# floppy_m0dule.net
KiCad netlist of a schematic drawn in Altium Designer
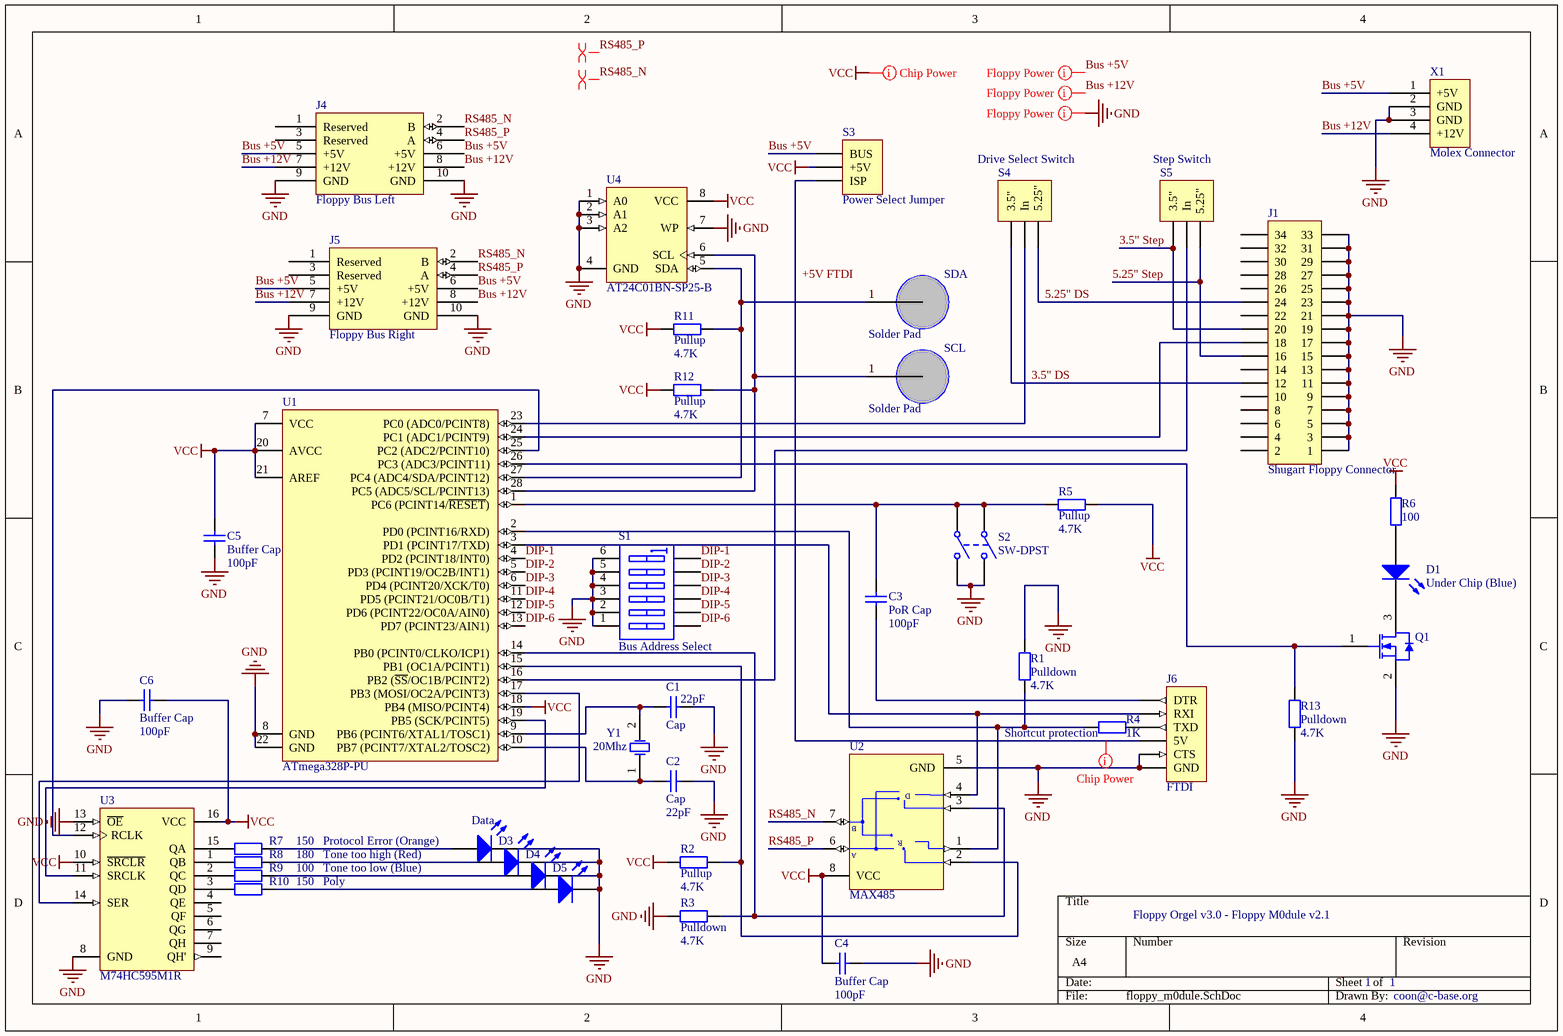
[diagram p0: floppy_m0dule.SchDoc]

(export (version "E")
  (design (tool "Eeschema 10.0.6"))
  (components
    (comp (ref "C1")
      (value "Cap")
      (footprint "RAD-0.1")
      (description "Capacitor")
      (fields (field (name "ALTIUM_VALUE") "22pF") (field (name "PUBLISHER") "Altium Limited"))
      (libsource (lib "Miscellaneous Devices") (part "Cap"))
    )
    (comp (ref "C2")
      (value "Cap")
      (footprint "RAD-0.1")
      (description "Capacitor")
      (fields (field (name "ALTIUM_VALUE") "22pF") (field (name "PUBLISHER") "Altium Limited"))
      (libsource (lib "Miscellaneous Devices") (part "Cap"))
    )
    (comp (ref "C3")
      (value "PoR Cap")
      (footprint "RAD-0.1")
      (description "Capacitor")
      (fields (field (name "ALTIUM_VALUE") "100pF") (field (name "PUBLISHER") "Altium Limited"))
      (libsource (lib "Miscellaneous Devices") (part "Cap"))
    )
    (comp (ref "C4")
      (value "Buffer Cap")
      (footprint "C1206")
      (description "Capacitor (Semiconductor SIM Model)")
      (fields (field (name "ALTIUM_VALUE") "100pF") (field (name "PUBLISHER") "Altium Limited"))
      (libsource (lib "Miscellaneous Devices") (part "Cap Semi"))
    )
    (comp (ref "C5")
      (value "Buffer Cap")
      (footprint "C1206")
      (description "Capacitor (Semiconductor SIM Model)")
      (fields (field (name "ALTIUM_VALUE") "100pF") (field (name "PUBLISHER") "Altium Limited"))
      (libsource (lib "Miscellaneous Devices") (part "Cap Semi"))
    )
    (comp (ref "C6")
      (value "Buffer Cap")
      (footprint "C1206")
      (description "Capacitor (Semiconductor SIM Model)")
      (fields (field (name "ALTIUM_VALUE") "100pF") (field (name "PUBLISHER") "Altium Limited"))
      (libsource (lib "Miscellaneous Devices") (part "Cap Semi"))
    )
    (comp (ref "D1")
      (value "Under Chip (Blue)")
      (footprint "0805 LED")
      (description "Typical BLUE SiC LED")
      (fields (field (name "PUBLISHER") "Altium Limited"))
      (libsource (lib "Miscellaneous Devices") (part "LED3"))
    )
    (comp (ref "D3")
      (value "Tone too high (Red)")
      (footprint "0805 LED")
      (description "Typical BLUE SiC LED")
      (fields (field (name "PUBLISHER") "Altium Limited"))
      (libsource (lib "Miscellaneous Devices") (part "LED3"))
    )
    (comp (ref "D4")
      (value "Tone too low (Blue)")
      (footprint "0805 LED")
      (description "Typical BLUE SiC LED")
      (fields (field (name "PUBLISHER") "Altium Limited"))
      (libsource (lib "Miscellaneous Devices") (part "LED3"))
    )
    (comp (ref "D5")
      (value "Poly")
      (footprint "0805 LED")
      (description "Typical BLUE SiC LED")
      (fields (field (name "PUBLISHER") "Altium Limited"))
      (libsource (lib "Miscellaneous Devices") (part "LED3"))
    )
    (comp (ref "Data")
      (value "Protocol Error (Orange)")
      (footprint "0805 LED")
      (description "Typical BLUE SiC LED")
      (fields (field (name "PUBLISHER") "Altium Limited"))
      (libsource (lib "Miscellaneous Devices") (part "LED3"))
    )
    (comp (ref "J1")
      (value "Shugart Floppy Connector")
      (footprint "HDR2X17")
      (description "Header, 17-Pin, Dual row")
      (fields (field (name "PUBLISHER") "Altium Limited"))
      (libsource (lib "Miscellaneous Connectors") (part "Header 17X2"))
    )
    (comp (ref "J4")
      (value "Floppy Bus Left")
      (footprint "Shrouded Pinheader 2x5")
      (description "10 Pin Floppy bus connector for rainbow cable")
      (fields (field (name "PUBLISHER") "Altium Limited"))
      (libsource (lib "floppyorgel") (part "Floppy Bus Connector"))
    )
    (comp (ref "J5")
      (value "Floppy Bus Right")
      (footprint "Shrouded Pinheader 2x5")
      (description "10 Pin Floppy bus connector for rainbow cable")
      (fields (field (name "PUBLISHER") "Altium Limited"))
      (libsource (lib "floppyorgel") (part "Floppy Bus Connector"))
    )
    (comp (ref "J6")
      (value "FTDI")
      (footprint "HDR1X6")
      (description "Header, 6-Pin")
      (fields (field (name "PUBLISHER") "Altium Limited"))
      (libsource (lib "Miscellaneous Connectors") (part "Header 6"))
    )
    (comp (ref "Q1")
      (value "IRLML6344TRPbF")
      (footprint "AO-SOT23-3_V")
      (description "N-channel Enhancement Mode Field-Effect Transistor; 5.8A/30V")
      (fields (field (name "MANUFACTURER") "Alpha and Omega") (field (name "PARTNUMBER") "AO3400"))
      (libsource (lib "Altium Content Vault") (part "AO-NEMOS-G1S2D3-3"))
    )
    (comp (ref "R1")
      (value "Pulldown")
      (footprint "AXIAL-0.4")
      (description "Resistor")
      (fields (field (name "ALTIUM_VALUE") "4.7K") (field (name "PUBLISHER") "Altium Limited"))
      (libsource (lib "") (part "Res2_1"))
    )
    (comp (ref "R2")
      (value "Pullup")
      (footprint "AXIAL-0.4")
      (description "Resistor")
      (fields (field (name "ALTIUM_VALUE") "4.7K") (field (name "PUBLISHER") "Altium Limited"))
      (libsource (lib "Miscellaneous Devices") (part "Res2"))
    )
    (comp (ref "R3")
      (value "Pulldown")
      (footprint "AXIAL-0.4")
      (description "Resistor")
      (fields (field (name "ALTIUM_VALUE") "4.7K") (field (name "PUBLISHER") "Altium Limited"))
      (libsource (lib "Miscellaneous Devices") (part "Res2"))
    )
    (comp (ref "R4")
      (value "Shortcut protection")
      (footprint "AXIAL-0.4")
      (description "Resistor")
      (fields (field (name "ALTIUM_VALUE") "1K") (field (name "PUBLISHER") "Altium Limited"))
      (libsource (lib "Miscellaneous Devices") (part "Res2"))
    )
    (comp (ref "R5")
      (value "Pullup")
      (footprint "AXIAL-0.4")
      (description "Resistor")
      (fields (field (name "ALTIUM_VALUE") "4.7K") (field (name "PUBLISHER") "Altium Limited"))
      (libsource (lib "Miscellaneous Devices") (part "Res2"))
    )
    (comp (ref "R6")
      (value "100")
      (footprint "R0805")
      (description "Resistor for Blue LED 17.5mA @ 5V")
      (fields (field (name "Comment") "LED res") (field (name "PUBLISHER") "Altium Limited"))
      (libsource (lib "") (part "Res2_1"))
    )
    (comp (ref "R7")
      (value "150")
      (footprint "R0805")
      (description "Resistor for Green LED 19.33mA @ 5V")
      (fields (field (name "Comment") "LED res") (field (name "PUBLISHER") "Altium Limited"))
      (libsource (lib "Miscellaneous Devices") (part "Res2"))
    )
    (comp (ref "R8")
      (value "180")
      (footprint "R0805")
      (description "Resistor for Blue LED 17.5mA @ 5V")
      (fields (field (name "Comment") "LED res") (field (name "PUBLISHER") "Altium Limited"))
      (libsource (lib "") (part "Res2_2"))
    )
    (comp (ref "R9")
      (value "100")
      (footprint "R0805")
      (description "Resistor for Blue LED 17.5mA @ 5V")
      (fields (field (name "Comment") "LED res") (field (name "PUBLISHER") "Altium Limited"))
      (libsource (lib "") (part "Res2_2"))
    )
    (comp (ref "R10")
      (value "150")
      (footprint "R0805")
      (description "Resistor for Blue LED 17.5mA @ 5V")
      (fields (field (name "Comment") "LED res") (field (name "PUBLISHER") "Altium Limited"))
      (libsource (lib "") (part "Res2_2"))
    )
    (comp (ref "R11")
      (value "Pullup")
      (footprint "R0805")
      (description "Resistor")
      (fields (field (name "ALTIUM_VALUE") "4.7K") (field (name "PUBLISHER") "Altium Limited"))
      (libsource (lib "Miscellaneous Devices") (part "Res2"))
    )
    (comp (ref "R12")
      (value "Pullup")
      (footprint "R0805")
      (description "Resistor")
      (fields (field (name "ALTIUM_VALUE") "4.7K") (field (name "PUBLISHER") "Altium Limited"))
      (libsource (lib "Miscellaneous Devices") (part "Res2"))
    )
    (comp (ref "R13")
      (value "Pulldown")
      (footprint "R0805")
      (description "Resistor")
      (fields (field (name "ALTIUM_VALUE") "4.7K") (field (name "PUBLISHER") "Altium Limited"))
      (libsource (lib "") (part "Res2_1"))
    )
    (comp (ref "S1")
      (value "Bus Address Select")
      (footprint "418117170906")
      (description "Midi Channel Select")
      (fields (field (name "PUBLISHER") "Altium Limited"))
      (libsource (lib "Miscellaneous Devices") (part "SW DIP-6"))
    )
    (comp (ref "S2")
      (value "SW-DPST")
      (footprint "SWITCH")
      (description "Double-Pole, Single-Throw Switch")
      (fields (field (name "PUBLISHER") "Altium Limited"))
      (libsource (lib "Miscellaneous Devices") (part "SW-DPST"))
    )
    (comp (ref "S3")
      (value "Power Select Jumper")
      (footprint "HDR1X3")
      (description "Header, 3-Pin, Right Angle")
      (fields (field (name "PUBLISHER") "Altium Limited"))
      (libsource (lib "Miscellaneous Connectors") (part "Header 3H"))
    )
    (comp (ref "S4")
      (value "Drive Select Switch")
      (footprint "0805 SMD Switch Pads")
      (description "Header, 3-Pin")
      (fields (field (name "PUBLISHER") "Altium Limited"))
      (libsource (lib "Miscellaneous Connectors") (part "Header 3"))
    )
    (comp (ref "S5")
      (value "Step Switch")
      (footprint "0805 SMD Switch Pads")
      (description "Header, 3-Pin")
      (fields (field (name "PUBLISHER") "Altium Limited"))
      (libsource (lib "Miscellaneous Connectors") (part "Header 3"))
    )
    (comp (ref "SCL")
      (value "Solder Pad")
      (footprint "SOLDER_PAD")
      (libsource (lib "floppy_m0dule") (part "Solder Pad"))
    )
    (comp (ref "SDA")
      (value "Solder Pad")
      (footprint "SOLDER_PAD")
      (libsource (lib "floppy_m0dule") (part "Solder Pad"))
    )
    (comp (ref "U1")
      (value "ATmega328P-PU")
      (footprint "28P3")
      (fields (field (name "PUBLISHER") "Altium Limited"))
      (libsource (lib "Atmel Microcontroller 8-Bit megaAVR") (part "ATmega328P-PU"))
    )
    (comp (ref "U2")
      (value "MAX485")
      (footprint "PA8")
      (description "Low-Power, Slew-Rate-Limited RS-485/RS-422 Transceiver")
      (fields (field (name "PUBLISHER") "Altium Limited"))
      (libsource (lib "Maxim Communication Transceiver") (part "MAX485EPA"))
    )
    (comp (ref "U3")
      (value "M74HC595M1R")
      (footprint "SO16_N")
      (description "8 Bit Shift Register with Output Latches (3 STATE)")
      (fields (field (name "PUBLISHER") "Altium Limited"))
      (libsource (lib "ST Logic Register") (part "M74HC595M1R"))
    )
    (comp (ref "U4")
      (value "AT24C01BN-SP25-B")
      (footprint "8S1_N")
      (description "1Kbit (128 x 8), 2-wire Bus Automotive Serial EEPROM with Write Protect, 2.5V, 8-Pin SOIC, Bulk")
      (fields (field (name "PUBLISHER") "Altium Limited"))
      (libsource (lib "Atmel Memory Serial EEPROM") (part "AT24C01BN-SP25-B"))
    )
    (comp (ref "X1")
      (value "Molex Connector")
      (footprint "HDR1X4")
      (description "Molex Power Supply Connector")
      (fields (field (name "PUBLISHER") "Altium Limited"))
      (libsource (lib "floppyorgel") (part "Molex Connector"))
    )
    (comp (ref "Y1")
      (value "20Mhz")
      (footprint "crystal")
      (description "Crystal Oscillator")
      (fields (field (name "PUBLISHER") "Altium Limited"))
      (libsource (lib "Miscellaneous Devices") (part "XTAL"))
    )
  )
  (nets
    (net (code "2") (name "/3.5\" DS") (class "Default")
      (node (ref "J1") (pin "12") (pinfunction "12_12") (pintype "passive"))
      (node (ref "S4") (pin "1") (pinfunction "3.5\"_1") (pintype "passive"))
    )
    (net (code "3") (name "/3.5\" Step") (class "Default")
      (node (ref "J1") (pin "20") (pinfunction "20_20") (pintype "passive"))
      (node (ref "S5") (pin "1") (pinfunction "3.5\"_1") (pintype "passive"))
    )
    (net (code "4") (name "/5.25\" DS") (class "Default")
      (node (ref "J1") (pin "24") (pinfunction "24_24") (pintype "passive"))
      (node (ref "S4") (pin "3") (pinfunction "5.25\"_3") (pintype "passive"))
    )
    (net (code "5") (name "/5.25\" Step") (class "Default")
      (node (ref "J1") (pin "16") (pinfunction "16_16") (pintype "passive"))
      (node (ref "S5") (pin "3") (pinfunction "5.25\"_3") (pintype "passive"))
    )
    (net (code "6") (name "/Bus +5V") (class "Default")
      (node (ref "J4") (pin "5") (pinfunction "+5V_5") (pintype "passive"))
      (node (ref "J4") (pin "6") (pinfunction "+5V_6") (pintype "power_in"))
      (node (ref "J5") (pin "5") (pinfunction "+5V_5") (pintype "passive"))
      (node (ref "J5") (pin "6") (pinfunction "+5V_6") (pintype "power_in"))
      (node (ref "S3") (pin "1") (pinfunction "BUS_1") (pintype "power_in"))
      (node (ref "X1") (pin "1") (pinfunction "+5V_1") (pintype "power_in"))
    )
    (net (code "7") (name "/Bus +12V") (class "Default")
      (node (ref "J4") (pin "7") (pinfunction "+12V_7") (pintype "passive"))
      (node (ref "J4") (pin "8") (pinfunction "+12V_8") (pintype "power_in"))
      (node (ref "J5") (pin "7") (pinfunction "+12V_7") (pintype "passive"))
      (node (ref "J5") (pin "8") (pinfunction "+12V_8") (pintype "power_in"))
      (node (ref "X1") (pin "4") (pinfunction "+12V_4") (pintype "power_in"))
    )
    (net (code "8") (name "/DIP-1") (class "Default")
      (node (ref "S1") (pin "12") (pinfunction "B1_12") (pintype "passive"))
      (node (ref "U1") (pin "4") (pinfunction "PD2_(PCINT18/INT0)_4") (pintype "bidirectional"))
    )
    (net (code "9") (name "/DIP-2") (class "Default")
      (node (ref "S1") (pin "11") (pinfunction "B2_11") (pintype "passive"))
      (node (ref "U1") (pin "5") (pinfunction "PD3_(PCINT19/OC2B/INT1)_5") (pintype "bidirectional"))
    )
    (net (code "10") (name "/DIP-3") (class "Default")
      (node (ref "S1") (pin "10") (pinfunction "B3_10") (pintype "passive"))
      (node (ref "U1") (pin "6") (pinfunction "PD4_(PCINT20/XCK/T0)_6") (pintype "bidirectional"))
    )
    (net (code "11") (name "/DIP-4") (class "Default")
      (node (ref "S1") (pin "9") (pinfunction "B4_9") (pintype "passive"))
      (node (ref "U1") (pin "11") (pinfunction "PD5_(PCINT21/OC0B/T1)_11") (pintype "bidirectional"))
    )
    (net (code "12") (name "/DIP-5") (class "Default")
      (node (ref "S1") (pin "8") (pinfunction "B5_8") (pintype "passive"))
      (node (ref "U1") (pin "12") (pinfunction "PD6_(PCINT22/OC0A/AIN0)_12") (pintype "bidirectional"))
    )
    (net (code "13") (name "/DIP-6") (class "Default")
      (node (ref "S1") (pin "7") (pinfunction "B6_7") (pintype "passive"))
      (node (ref "U1") (pin "13") (pinfunction "PD7_(PCINT23/AIN1)_13") (pintype "bidirectional"))
    )
    (net (code "14") (name "/RS485_N") (class "Default")
      (node (ref "J4") (pin "2") (pinfunction "B_2") (pintype "bidirectional"))
      (node (ref "J5") (pin "2") (pinfunction "B_2") (pintype "bidirectional"))
      (node (ref "U2") (pin "7") (pinfunction "B_7") (pintype "bidirectional"))
    )
    (net (code "15") (name "/RS485_P") (class "Default")
      (node (ref "J4") (pin "4") (pinfunction "A_4") (pintype "bidirectional"))
      (node (ref "J5") (pin "4") (pinfunction "A_4") (pintype "bidirectional"))
      (node (ref "U2") (pin "6") (pinfunction "A_6") (pintype "bidirectional"))
    )
    (net (code "16") (name "GND") (class "Default")
      (node (ref "C1") (pin "2") (pinfunction "2_2") (pintype "passive"))
      (node (ref "C2") (pin "2") (pinfunction "2_2") (pintype "passive"))
      (node (ref "C4") (pin "1") (pinfunction "1_1") (pintype "passive"))
      (node (ref "C5") (pin "1") (pinfunction "1_1") (pintype "passive"))
      (node (ref "C6") (pin "1") (pinfunction "1_1") (pintype "passive"))
      (node (ref "D3") (pin "2") (pinfunction "K_2") (pintype "passive"))
      (node (ref "D4") (pin "2") (pinfunction "K_2") (pintype "passive"))
      (node (ref "D5") (pin "2") (pinfunction "K_2") (pintype "passive"))
      (node (ref "Data") (pin "2") (pinfunction "K_2") (pintype "passive"))
      (node (ref "J1") (pin "1") (pinfunction "1_1") (pintype "passive"))
      (node (ref "J1") (pin "11") (pinfunction "11_11") (pintype "passive"))
      (node (ref "J1") (pin "13") (pinfunction "13_13") (pintype "passive"))
      (node (ref "J1") (pin "15") (pinfunction "15_15") (pintype "passive"))
      (node (ref "J1") (pin "17") (pinfunction "17_17") (pintype "passive"))
      (node (ref "J1") (pin "19") (pinfunction "19_19") (pintype "passive"))
      (node (ref "J1") (pin "21") (pinfunction "21_21") (pintype "passive"))
      (node (ref "J1") (pin "23") (pinfunction "23_23") (pintype "passive"))
      (node (ref "J1") (pin "25") (pinfunction "25_25") (pintype "passive"))
      (node (ref "J1") (pin "27") (pinfunction "27_27") (pintype "passive"))
      (node (ref "J1") (pin "29") (pinfunction "29_29") (pintype "passive"))
      (node (ref "J1") (pin "3") (pinfunction "3_3") (pintype "passive"))
      (node (ref "J1") (pin "31") (pinfunction "31_31") (pintype "passive"))
      (node (ref "J1") (pin "33") (pinfunction "33_33") (pintype "passive"))
      (node (ref "J1") (pin "5") (pinfunction "5_5") (pintype "passive"))
      (node (ref "J1") (pin "7") (pinfunction "7_7") (pintype "passive"))
      (node (ref "J1") (pin "9") (pinfunction "9_9") (pintype "passive"))
      (node (ref "J4") (pin "10") (pinfunction "GND_10") (pintype "passive"))
      (node (ref "J4") (pin "9") (pinfunction "GND_9") (pintype "power_in"))
      (node (ref "J5") (pin "10") (pinfunction "GND_10") (pintype "passive"))
      (node (ref "J5") (pin "9") (pinfunction "GND_9") (pintype "power_in"))
      (node (ref "J6") (pin "5") (pinfunction "CTS_5") (pintype "input"))
      (node (ref "J6") (pin "6") (pinfunction "GND_6") (pintype "power_in"))
      (node (ref "Q1") (pin "2") (pinfunction "S_2") (pintype "passive"))
      (node (ref "R1") (pin "2") (pinfunction "2_2") (pintype "passive"))
      (node (ref "R13") (pin "1") (pinfunction "1_1") (pintype "passive"))
      (node (ref "R3") (pin "1") (pinfunction "1_1") (pintype "passive"))
      (node (ref "S1") (pin "1") (pinfunction "A1_1") (pintype "passive"))
      (node (ref "S1") (pin "2") (pinfunction "A2_2") (pintype "passive"))
      (node (ref "S1") (pin "3") (pinfunction "A3_3") (pintype "passive"))
      (node (ref "S1") (pin "4") (pinfunction "A4_4") (pintype "passive"))
      (node (ref "S1") (pin "5") (pinfunction "A5_5") (pintype "passive"))
      (node (ref "S1") (pin "6") (pinfunction "A6_6") (pintype "passive"))
      (node (ref "S2") (pin "2") (pinfunction "NO1_2") (pintype "passive"))
      (node (ref "S2") (pin "4") (pinfunction "NO2_4") (pintype "passive"))
      (node (ref "U1") (pin "22") (pinfunction "GND_22") (pintype "power_in"))
      (node (ref "U1") (pin "8") (pinfunction "GND_8") (pintype "power_in"))
      (node (ref "U2") (pin "5") (pinfunction "GND_5") (pintype "power_in"))
      (node (ref "U3") (pin "13") (pinfunction "~{OE}_13") (pintype "input"))
      (node (ref "U3") (pin "8") (pinfunction "GND_8") (pintype "power_in"))
      (node (ref "U4") (pin "1") (pinfunction "A0_1") (pintype "input"))
      (node (ref "U4") (pin "2") (pinfunction "A1_2") (pintype "input"))
      (node (ref "U4") (pin "3") (pinfunction "A2_3") (pintype "input"))
      (node (ref "U4") (pin "4") (pinfunction "GND_4") (pintype "power_in"))
      (node (ref "U4") (pin "7") (pinfunction "WP_7") (pintype "input"))
      (node (ref "X1") (pin "2") (pinfunction "GND_2") (pintype "power_in"))
      (node (ref "X1") (pin "3") (pinfunction "GND_3") (pintype "power_in"))
    )
    (net (code "17") (name "Net-(D1-A)") (class "Default")
      (node (ref "D1") (pin "1") (pinfunction "A_1") (pintype "passive"))
      (node (ref "R6") (pin "1") (pinfunction "1_1") (pintype "passive"))
    )
    (net (code "18") (name "Net-(D1-K)") (class "Default")
      (node (ref "D1") (pin "2") (pinfunction "K_2") (pintype "passive"))
      (node (ref "Q1") (pin "3") (pinfunction "D_3") (pintype "passive"))
    )
    (net (code "19") (name "Net-(D3-A)") (class "Default")
      (node (ref "D3") (pin "1") (pinfunction "A_1") (pintype "passive"))
      (node (ref "R8") (pin "1") (pinfunction "1_1") (pintype "passive"))
    )
    (net (code "20") (name "Net-(D4-A)") (class "Default")
      (node (ref "D4") (pin "1") (pinfunction "A_1") (pintype "passive"))
      (node (ref "R9") (pin "1") (pinfunction "1_1") (pintype "passive"))
    )
    (net (code "21") (name "Net-(D5-A)") (class "Default")
      (node (ref "D5") (pin "1") (pinfunction "A_1") (pintype "passive"))
      (node (ref "R10") (pin "1") (pinfunction "1_1") (pintype "passive"))
    )
    (net (code "22") (name "Net-(Data-A)") (class "Default")
      (node (ref "Data") (pin "1") (pinfunction "A_1") (pintype "passive"))
      (node (ref "R7") (pin "2") (pinfunction "2_2") (pintype "passive"))
    )
    (net (code "23") (name "Net-(J6-5V)") (class "Default")
      (node (ref "J6") (pin "4") (pinfunction "5V_4") (pintype "power_in"))
      (node (ref "S3") (pin "3") (pinfunction "ISP_3") (pintype "power_in"))
    )
    (net (code "24") (name "Net-(J6-DTR)") (class "Default")
      (node (ref "C3") (pin "1") (pinfunction "1_1") (pintype "passive"))
      (node (ref "J6") (pin "1") (pinfunction "DTR_1") (pintype "output"))
    )
    (net (code "25") (name "Net-(J6-RXI)") (class "Default")
      (node (ref "J6") (pin "2") (pinfunction "RXI_2") (pintype "input"))
      (node (ref "U1") (pin "3") (pinfunction "PD1_(PCINT17/TXD)_3") (pintype "bidirectional"))
      (node (ref "U2") (pin "4") (pinfunction "DI_4") (pintype "input"))
    )
    (net (code "26") (name "Net-(J6-TXD)") (class "Default")
      (node (ref "J6") (pin "3") (pinfunction "TXD_3") (pintype "output"))
      (node (ref "R4") (pin "2") (pinfunction "2_2") (pintype "passive"))
    )
    (net (code "27") (name "Net-(Q1-G)") (class "Default")
      (node (ref "Q1") (pin "1") (pinfunction "G_1") (pintype "passive"))
      (node (ref "R13") (pin "2") (pinfunction "2_2") (pintype "passive"))
      (node (ref "U1") (pin "26") (pinfunction "PC3_(ADC3/PCINT11)_26") (pintype "bidirectional"))
    )
    (net (code "28") (name "Net-(S2-COMMON1)") (class "Default")
      (node (ref "C3") (pin "2") (pinfunction "2_2") (pintype "passive"))
      (node (ref "R5") (pin "1") (pinfunction "1_1") (pintype "passive"))
      (node (ref "S2") (pin "1") (pinfunction "COMMON1_1") (pintype "passive"))
      (node (ref "S2") (pin "3") (pinfunction "COMMON2_3") (pintype "passive"))
      (node (ref "U1") (pin "1") (pinfunction "PC6_(PCINT14/~{RESET})_1") (pintype "bidirectional"))
    )
    (net (code "29") (name "Net-(S4-In)") (class "Default")
      (node (ref "S4") (pin "2") (pinfunction "In_2") (pintype "passive"))
      (node (ref "U1") (pin "23") (pinfunction "PC0_(ADC0/PCINT8)_23") (pintype "bidirectional"))
    )
    (net (code "30") (name "Net-(S5-In)") (class "Default")
      (node (ref "S5") (pin "2") (pinfunction "In_2") (pintype "passive"))
      (node (ref "U1") (pin "16") (pinfunction "PB2_(~{SS}/OC1B/PCINT2)_16") (pintype "bidirectional"))
    )
    (net (code "31") (name "Net-(U1-PB0_(PCINT0{slash}CLKO{slash}ICP1))") (class "Default")
      (node (ref "R3") (pin "2") (pinfunction "2_2") (pintype "passive"))
      (node (ref "U1") (pin "14") (pinfunction "PB0_(PCINT0/CLKO/ICP1)_14") (pintype "bidirectional"))
      (node (ref "U2") (pin "3") (pinfunction "DE_3") (pintype "input"))
    )
    (net (code "32") (name "Net-(U1-PB1_(OC1A{slash}PCINT1))") (class "Default")
      (node (ref "R2") (pin "2") (pinfunction "2_2") (pintype "passive"))
      (node (ref "U1") (pin "15") (pinfunction "PB1_(OC1A/PCINT1)_15") (pintype "bidirectional"))
      (node (ref "U2") (pin "2") (pinfunction "~{RE}_2") (pintype "input"))
    )
    (net (code "33") (name "Net-(U1-PB3_(MOSI{slash}OC2A{slash}PCINT3))") (class "Default")
      (node (ref "U1") (pin "17") (pinfunction "PB3_(MOSI/OC2A/PCINT3)_17") (pintype "bidirectional"))
      (node (ref "U3") (pin "14") (pinfunction "SER_14") (pintype "input"))
    )
    (net (code "34") (name "Net-(U1-PB5_(SCK{slash}PCINT5))") (class "Default")
      (node (ref "U1") (pin "19") (pinfunction "PB5_(SCK/PCINT5)_19") (pintype "bidirectional"))
      (node (ref "U3") (pin "11") (pinfunction "SRCLK_11") (pintype "input"))
    )
    (net (code "35") (name "Net-(U1-PB6_(PCINT6{slash}XTAL1{slash}TOSC1))") (class "Default")
      (node (ref "C1") (pin "1") (pinfunction "1_1") (pintype "passive"))
      (node (ref "U1") (pin "9") (pinfunction "PB6_(PCINT6/XTAL1/TOSC1)_9") (pintype "bidirectional"))
      (node (ref "Y1") (pin "2") (pinfunction "OSC2_2") (pintype "passive"))
    )
    (net (code "36") (name "Net-(U1-PB7_(PCINT7{slash}XTAL2{slash}TOSC2))") (class "Default")
      (node (ref "C2") (pin "1") (pinfunction "1_1") (pintype "passive"))
      (node (ref "U1") (pin "10") (pinfunction "PB7_(PCINT7/XTAL2/TOSC2)_10") (pintype "bidirectional"))
      (node (ref "Y1") (pin "1") (pinfunction "OSC1_1") (pintype "passive"))
    )
    (net (code "37") (name "Net-(U1-PC1_(ADC1{slash}PCINT9))") (class "Default")
      (node (ref "J1") (pin "18") (pinfunction "18_18") (pintype "passive"))
      (node (ref "U1") (pin "24") (pinfunction "PC1_(ADC1/PCINT9)_24") (pintype "bidirectional"))
    )
    (net (code "38") (name "Net-(U1-PC2_(ADC2{slash}PCINT10))") (class "Default")
      (node (ref "U1") (pin "25") (pinfunction "PC2_(ADC2/PCINT10)_25") (pintype "bidirectional"))
      (node (ref "U3") (pin "12") (pinfunction "RCLK_12") (pintype "input"))
    )
    (net (code "39") (name "Net-(U1-PC4_(ADC4{slash}SDA{slash}PCINT12))") (class "Default")
      (node (ref "R11") (pin "2") (pinfunction "2_2") (pintype "passive"))
      (node (ref "SDA") (pin "1") (pinfunction "1_1") (pintype "passive"))
      (node (ref "U1") (pin "27") (pinfunction "PC4_(ADC4/SDA/PCINT12)_27") (pintype "bidirectional"))
      (node (ref "U4") (pin "5") (pinfunction "SDA_5") (pintype "bidirectional"))
    )
    (net (code "40") (name "Net-(U1-PC5_(ADC5{slash}SCL{slash}PCINT13))") (class "Default")
      (node (ref "R12") (pin "2") (pinfunction "2_2") (pintype "passive"))
      (node (ref "SCL") (pin "1") (pinfunction "1_1") (pintype "passive"))
      (node (ref "U1") (pin "28") (pinfunction "PC5_(ADC5/SCL/PCINT13)_28") (pintype "bidirectional"))
      (node (ref "U4") (pin "6") (pinfunction "SCL_6") (pintype "input"))
    )
    (net (code "41") (name "Net-(U1-PD0_(PCINT16{slash}RXD))") (class "Default")
      (node (ref "R1") (pin "1") (pinfunction "1_1") (pintype "passive"))
      (node (ref "R4") (pin "1") (pinfunction "1_1") (pintype "passive"))
      (node (ref "U1") (pin "2") (pinfunction "PD0_(PCINT16/RXD)_2") (pintype "bidirectional"))
      (node (ref "U2") (pin "1") (pinfunction "RO_1") (pintype "output"))
    )
    (net (code "42") (name "Net-(U3-QA)") (class "Default")
      (node (ref "R7") (pin "1") (pinfunction "1_1") (pintype "passive"))
      (node (ref "U3") (pin "15") (pinfunction "QA_15") (pintype "tri_state"))
    )
    (net (code "43") (name "Net-(U3-QB)") (class "Default")
      (node (ref "R8") (pin "2") (pinfunction "2_2") (pintype "passive"))
      (node (ref "U3") (pin "1") (pinfunction "QB_1") (pintype "tri_state"))
    )
    (net (code "44") (name "Net-(U3-QC)") (class "Default")
      (node (ref "R9") (pin "2") (pinfunction "2_2") (pintype "passive"))
      (node (ref "U3") (pin "2") (pinfunction "QC_2") (pintype "tri_state"))
    )
    (net (code "45") (name "Net-(U3-QD)") (class "Default")
      (node (ref "R10") (pin "2") (pinfunction "2_2") (pintype "passive"))
      (node (ref "U3") (pin "3") (pinfunction "QD_3") (pintype "tri_state"))
    )
    (net (code "46") (name "VCC") (class "Default")
      (node (ref "C4") (pin "2") (pinfunction "2_2") (pintype "passive"))
      (node (ref "C5") (pin "2") (pinfunction "2_2") (pintype "passive"))
      (node (ref "C6") (pin "2") (pinfunction "2_2") (pintype "passive"))
      (node (ref "R11") (pin "1") (pinfunction "1_1") (pintype "passive"))
      (node (ref "R12") (pin "1") (pinfunction "1_1") (pintype "passive"))
      (node (ref "R2") (pin "1") (pinfunction "1_1") (pintype "passive"))
      (node (ref "R5") (pin "2") (pinfunction "2_2") (pintype "passive"))
      (node (ref "R6") (pin "2") (pinfunction "2_2") (pintype "passive"))
      (node (ref "S3") (pin "2") (pinfunction "+5V_2") (pintype "power_in"))
      (node (ref "U1") (pin "18") (pinfunction "PB4_(MISO/PCINT4)_18") (pintype "bidirectional"))
      (node (ref "U1") (pin "20") (pinfunction "AVCC_20") (pintype "power_in"))
      (node (ref "U1") (pin "21") (pinfunction "AREF_21") (pintype "power_in"))
      (node (ref "U1") (pin "7") (pinfunction "VCC_7") (pintype "power_in"))
      (node (ref "U2") (pin "8") (pinfunction "VCC_8") (pintype "power_in"))
      (node (ref "U3") (pin "10") (pinfunction "~{SRCLR}_10") (pintype "input"))
      (node (ref "U3") (pin "16") (pinfunction "VCC_16") (pintype "power_in"))
      (node (ref "U4") (pin "8") (pinfunction "VCC_8") (pintype "power_in"))
    )
    (net (code "47") (name "unconnected-(J1-Pad2)") (class "Default")
      (node (ref "J1") (pin "2") (pinfunction "2_2") (pintype "passive"))
    )
    (net (code "48") (name "unconnected-(J1-Pad4)") (class "Default")
      (node (ref "J1") (pin "4") (pinfunction "4_4") (pintype "passive"))
    )
    (net (code "49") (name "unconnected-(J1-Pad6)") (class "Default")
      (node (ref "J1") (pin "6") (pinfunction "6_6") (pintype "passive"))
    )
    (net (code "50") (name "unconnected-(J1-Pad8)") (class "Default")
      (node (ref "J1") (pin "8") (pinfunction "8_8") (pintype "passive"))
    )
    (net (code "51") (name "unconnected-(J1-Pad10)") (class "Default")
      (node (ref "J1") (pin "10") (pinfunction "10_10") (pintype "passive"))
    )
    (net (code "52") (name "unconnected-(J1-Pad14)") (class "Default")
      (node (ref "J1") (pin "14") (pinfunction "14_14") (pintype "passive"))
    )
    (net (code "53") (name "unconnected-(J1-Pad22)") (class "Default")
      (node (ref "J1") (pin "22") (pinfunction "22_22") (pintype "passive"))
    )
    (net (code "54") (name "unconnected-(J1-Pad26)") (class "Default")
      (node (ref "J1") (pin "26") (pinfunction "26_26") (pintype "passive"))
    )
    (net (code "55") (name "unconnected-(J1-Pad28)") (class "Default")
      (node (ref "J1") (pin "28") (pinfunction "28_28") (pintype "passive"))
    )
    (net (code "56") (name "unconnected-(J1-Pad30)") (class "Default")
      (node (ref "J1") (pin "30") (pinfunction "30_30") (pintype "passive"))
    )
    (net (code "57") (name "unconnected-(J1-Pad32)") (class "Default")
      (node (ref "J1") (pin "32") (pinfunction "32_32") (pintype "passive"))
    )
    (net (code "58") (name "unconnected-(J1-Pad34)") (class "Default")
      (node (ref "J1") (pin "34") (pinfunction "34_34") (pintype "passive"))
    )
    (net (code "59") (name "unconnected-(J4-Reserved-Pad1)") (class "Default")
      (node (ref "J4") (pin "1") (pinfunction "Reserved_1") (pintype "passive"))
    )
    (net (code "60") (name "unconnected-(J4-Reserved-Pad3)") (class "Default")
      (node (ref "J4") (pin "3") (pinfunction "Reserved_3") (pintype "passive"))
    )
    (net (code "61") (name "unconnected-(J5-Reserved-Pad1)") (class "Default")
      (node (ref "J5") (pin "1") (pinfunction "Reserved_1") (pintype "passive"))
    )
    (net (code "62") (name "unconnected-(J5-Reserved-Pad3)") (class "Default")
      (node (ref "J5") (pin "3") (pinfunction "Reserved_3") (pintype "passive"))
    )
    (net (code "63") (name "unconnected-(U3-QE-Pad4)") (class "Default")
      (node (ref "U3") (pin "4") (pinfunction "QE_4") (pintype "tri_state"))
    )
    (net (code "64") (name "unconnected-(U3-QF-Pad5)") (class "Default")
      (node (ref "U3") (pin "5") (pinfunction "QF_5") (pintype "tri_state"))
    )
    (net (code "65") (name "unconnected-(U3-QG-Pad6)") (class "Default")
      (node (ref "U3") (pin "6") (pinfunction "QG_6") (pintype "tri_state"))
    )
    (net (code "66") (name "unconnected-(U3-QH'-Pad9)") (class "Default")
      (node (ref "U3") (pin "9") (pinfunction "QH'_9") (pintype "output"))
    )
    (net (code "67") (name "unconnected-(U3-QH-Pad7)") (class "Default")
      (node (ref "U3") (pin "7") (pinfunction "QH_7") (pintype "tri_state"))
    )
  )
)
